# ScoutMakes_Azul.net
KiCad netlist of a schematic drawn in EAGLE
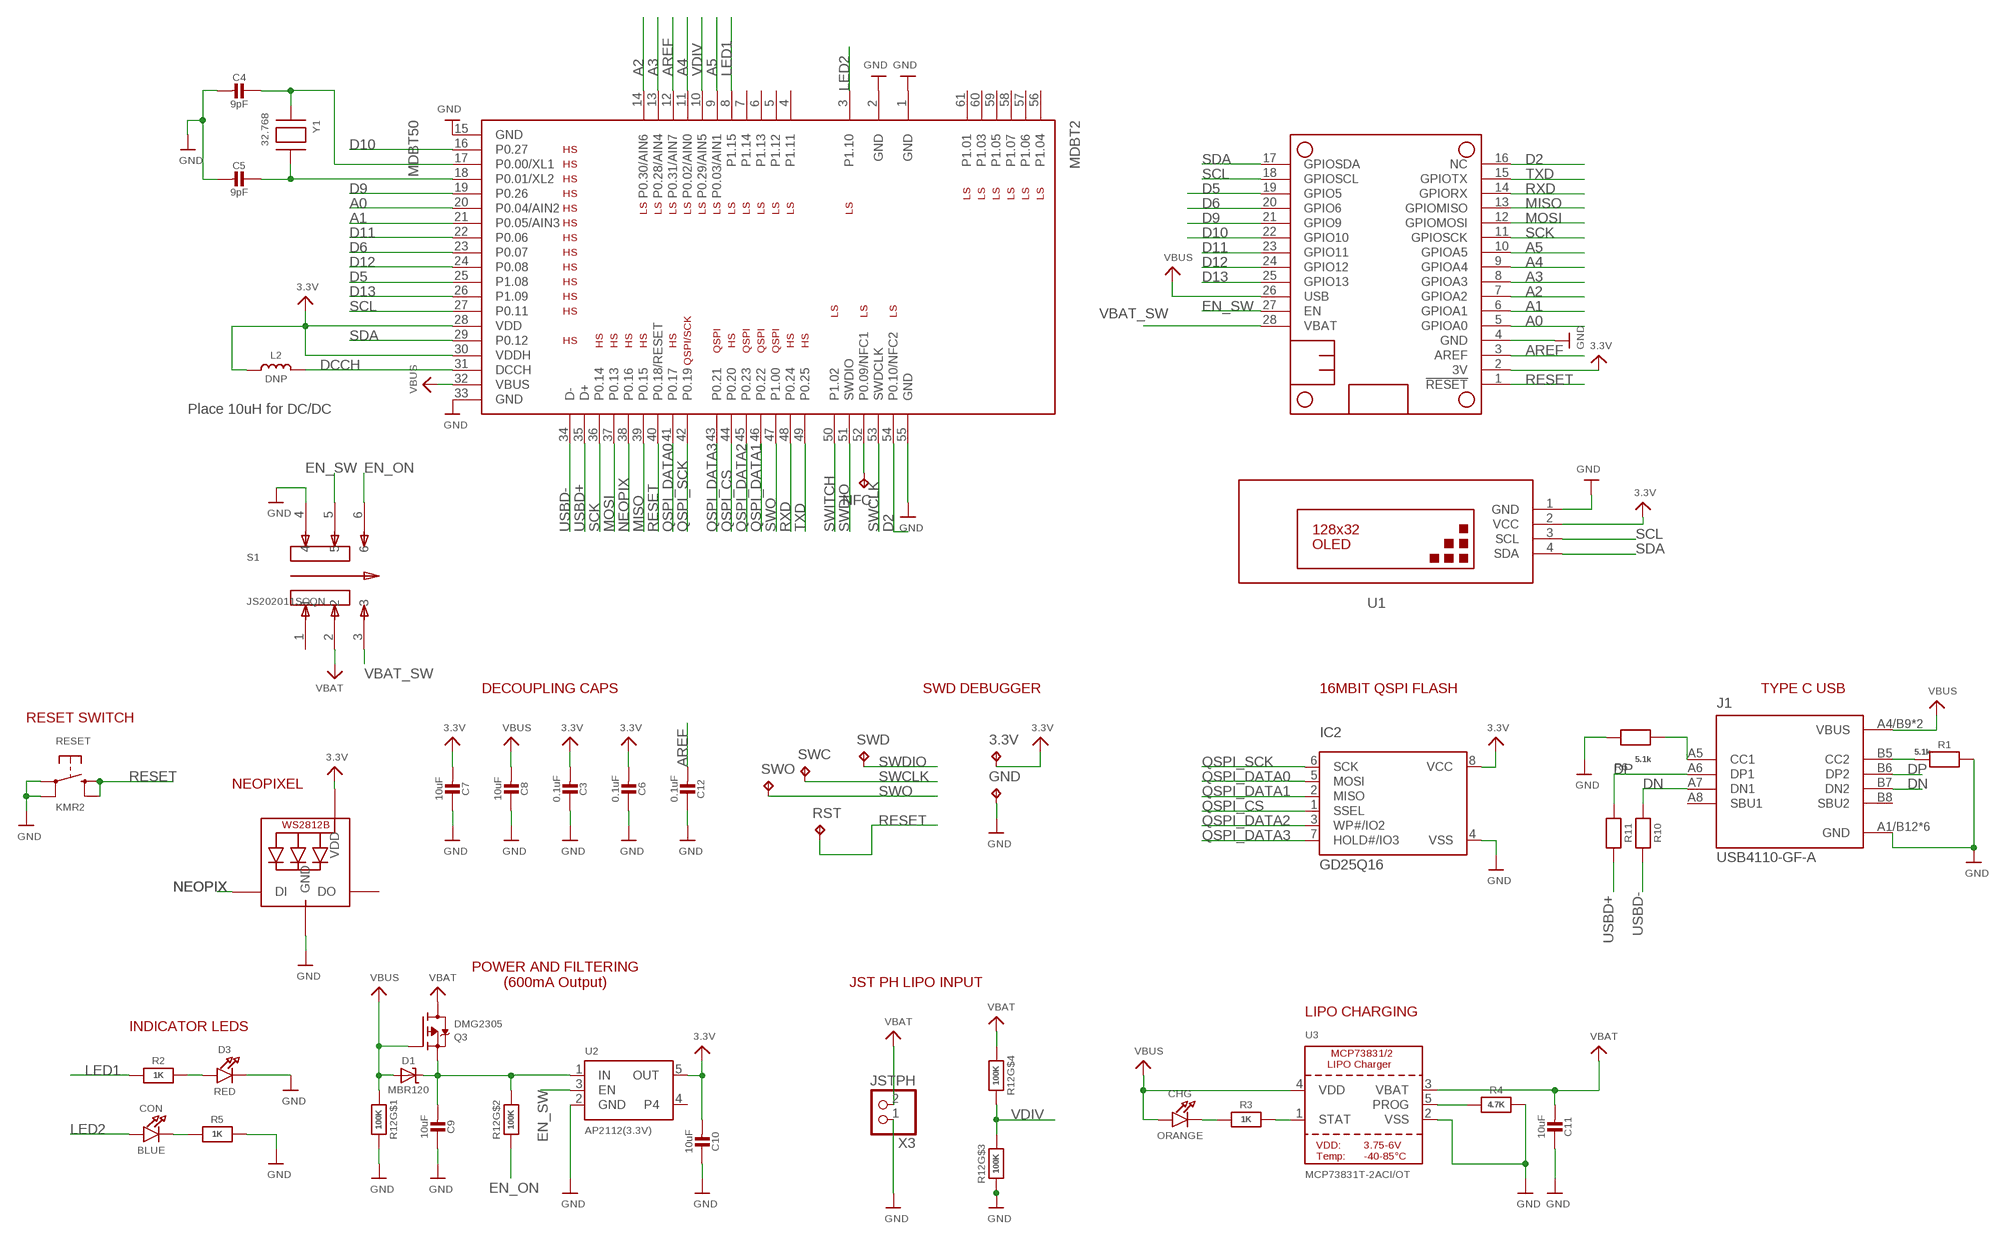
[diagram p0: schematic, sheet 1]

(export (version "E")
  (design (tool "Eeschema 10.0.6"))
  (components
    (comp (ref "3.3V")
      (value "TPTP12R")
      (footprint "eagle-import:TP12R")
      (libsource (lib "eagle-import") (part "TPTP12R"))
    )
    (comp (ref "C3")
      (value "0.1uF")
      (footprint "eagle-import:0603-NO")
      (libsource (lib "eagle-import") (part "CAP_CERAMIC0603_NO"))
    )
    (comp (ref "C4")
      (value "9pF")
      (footprint "eagle-import:0603-NO")
      (libsource (lib "eagle-import") (part "CAP_CERAMIC0603_NO"))
    )
    (comp (ref "C5")
      (value "9pF")
      (footprint "eagle-import:0603-NO")
      (libsource (lib "eagle-import") (part "CAP_CERAMIC0603_NO"))
    )
    (comp (ref "C6")
      (value "0.1uF")
      (footprint "eagle-import:0603-NO")
      (libsource (lib "eagle-import") (part "CAP_CERAMIC0603_NO"))
    )
    (comp (ref "C7")
      (value "10uF")
      (footprint "eagle-import:0805-NO")
      (libsource (lib "eagle-import") (part "CAP_CERAMIC0805-NOOUTLINE"))
    )
    (comp (ref "C8")
      (value "10uF")
      (footprint "eagle-import:0805-NO")
      (libsource (lib "eagle-import") (part "CAP_CERAMIC0805-NOOUTLINE"))
    )
    (comp (ref "C9")
      (value "10uF")
      (footprint "eagle-import:0805-NO")
      (libsource (lib "eagle-import") (part "CAP_CERAMIC0805-NOOUTLINE"))
    )
    (comp (ref "C10")
      (value "10uF")
      (footprint "eagle-import:0805-NO")
      (libsource (lib "eagle-import") (part "CAP_CERAMIC0805-NOOUTLINE"))
    )
    (comp (ref "C11")
      (value "10uF")
      (footprint "eagle-import:0805-NO")
      (libsource (lib "eagle-import") (part "CAP_CERAMIC0805-NOOUTLINE"))
    )
    (comp (ref "C12")
      (value "0.1uF")
      (footprint "eagle-import:0603-NO")
      (libsource (lib "eagle-import") (part "CAP_CERAMIC0603_NO"))
    )
    (comp (ref "CHG")
      (value "ORANGE")
      (footprint "eagle-import:CHIPLED_0805_NOOUTLINE")
      (libsource (lib "eagle-import") (part "LED0805_NOOUTLINE"))
    )
    (comp (ref "CON")
      (value "BLUE")
      (footprint "eagle-import:CHIPLED_0805_NOOUTLINE")
      (libsource (lib "eagle-import") (part "LED0805_NOOUTLINE"))
    )
    (comp (ref "D1")
      (value "MBR120")
      (footprint "eagle-import:SOD-123")
      (libsource (lib "eagle-import") (part "DIODE-SCHOTTKYSOD-123"))
    )
    (comp (ref "D3")
      (value "RED")
      (footprint "eagle-import:CHIPLED_0805_NOOUTLINE")
      (libsource (lib "eagle-import") (part "LED0805_NOOUTLINE"))
    )
    (comp (ref "GND")
      (value "TPTP12R")
      (footprint "eagle-import:TP12R")
      (libsource (lib "eagle-import") (part "TPTP12R"))
    )
    (comp (ref "IC2")
      (value "GD25Q16")
      (footprint "eagle-import:USON8")
      (libsource (lib "eagle-import") (part "SPIFLASH_8PINUX"))
    )
    (comp (ref "J1")
      (value "USB4110-GF-A")
      (footprint "eagle-import:GCT_USB4110-GF-A")
      (fields (field (name "MF") "GCT"))
      (libsource (lib "eagle-import") (part "USB4110-GF-A"))
    )
    (comp (ref "L2")
      (value "DNP")
      (footprint "eagle-import:_0805MP")
      (libsource (lib "eagle-import") (part "INDUCTOR_0805MP"))
    )
    (comp (ref "LED")
      (value "WS2812B3535")
      (footprint "eagle-import:LED3535")
      (libsource (lib "eagle-import") (part "WS2812B3535"))
    )
    (comp (ref "MDBT2")
      (value "MDBT50")
      (footprint "eagle-import:MDBT50")
      (libsource (lib "eagle-import") (part "MDBT50"))
    )
    (comp (ref "MS1")
      (value "FEATHERWING_NODIM")
      (footprint "eagle-import:FEATHERWING_NODIM")
      (libsource (lib "eagle-import") (part "FEATHERWING_NODIM"))
    )
    (comp (ref "NFC")
      (value "TPTP10R")
      (footprint "eagle-import:TP10R")
      (libsource (lib "eagle-import") (part "TPTP10R"))
    )
    (comp (ref "Q3")
      (value "DMG2305")
      (footprint "eagle-import:SOT23-R")
      (libsource (lib "eagle-import") (part "MOSFET-P"))
    )
    (comp (ref "R1")
      (value "5.1k")
      (footprint "eagle-import:0603-NO")
      (libsource (lib "eagle-import") (part "RESISTOR_0603_NOOUT"))
    )
    (comp (ref "R2")
      (value "1K")
      (footprint "eagle-import:0603-NO")
      (libsource (lib "eagle-import") (part "RESISTOR_0603_NOOUT"))
    )
    (comp (ref "R3")
      (value "1K")
      (footprint "eagle-import:0603-NO")
      (libsource (lib "eagle-import") (part "RESISTOR_0603_NOOUT"))
    )
    (comp (ref "R4")
      (value "4.7K")
      (footprint "eagle-import:0603-NO")
      (libsource (lib "eagle-import") (part "RESISTOR_0603_NOOUT"))
    )
    (comp (ref "R5")
      (value "1K")
      (footprint "eagle-import:0603-NO")
      (libsource (lib "eagle-import") (part "RESISTOR_0603_NOOUT"))
    )
    (comp (ref "R6")
      (value "5.1k")
      (footprint "eagle-import:0603-NO")
      (libsource (lib "eagle-import") (part "RESISTOR_0603_NOOUT"))
    )
    (comp (ref "R10")
      (value "22")
      (footprint "eagle-import:0603-NO")
      (libsource (lib "eagle-import") (part "RESISTOR_0603_NOOUT"))
    )
    (comp (ref "R11")
      (value "22")
      (footprint "eagle-import:0603-NO")
      (libsource (lib "eagle-import") (part "RESISTOR_0603_NOOUT"))
    )
    (comp (ref "R12")
      (value "100K")
      (footprint "eagle-import:RESPACK_4X0603")
      (libsource (lib "eagle-import") (part "RESISTOR_4PACK"))
    )
    (comp (ref "RESET")
      (value "KMR2")
      (footprint "eagle-import:BTN_KMR2_4.6X2.8")
      (libsource (lib "eagle-import") (part "SWITCH_TACT_SMT4.6X2.8"))
    )
    (comp (ref "RST")
      (value "TPTP12R")
      (footprint "eagle-import:TP12R")
      (libsource (lib "eagle-import") (part "TPTP12R"))
    )
    (comp (ref "S1")
      (value "JS202011SCQN")
      (footprint "eagle-import:SW_JS202011SCQN")
      (fields (field (name "DIGI-KEY_PART_NUMBER") "401-2002-1-ND") (field (name "MF") "C&K"))
      (libsource (lib "eagle-import") (part "JS202011SCQN"))
    )
    (comp (ref "SWC")
      (value "TPTP12R")
      (footprint "eagle-import:TP12R")
      (libsource (lib "eagle-import") (part "TPTP12R"))
    )
    (comp (ref "SWD")
      (value "TPTP12R")
      (footprint "eagle-import:TP12R")
      (libsource (lib "eagle-import") (part "TPTP12R"))
    )
    (comp (ref "SWO")
      (value "TPTP12R")
      (footprint "eagle-import:TP12R")
      (libsource (lib "eagle-import") (part "TPTP12R"))
    )
    (comp (ref "U1")
      (value "DISPLAY-OLED-128X32")
      (footprint "eagle-import:DISPLAY-OLED-128X32")
      (libsource (lib "eagle-import") (part "DISPLAY-OLED-128X32"))
    )
    (comp (ref "U2")
      (value "AP2112(3.3V)")
      (footprint "eagle-import:SOT23-5")
      (libsource (lib "eagle-import") (part "VREG_SOT23-5"))
    )
    (comp (ref "U3")
      (value "MCP73831T-2ACI/OT")
      (footprint "eagle-import:SOT23-5")
      (libsource (lib "eagle-import") (part "MCP73831/2"))
    )
    (comp (ref "X3")
      (value "JSTPH")
      (footprint "eagle-import:JSTPH2")
      (libsource (lib "eagle-import") (part "CON_JST_PH_2PIN"))
    )
    (comp (ref "Y1")
      (value "32.768")
      (footprint "eagle-import:XTAL3215")
      (libsource (lib "eagle-import") (part "XTAL-3.2X1.5"))
    )
  )
  (nets
    (net (code "1") (name "/A0") (class "Default")
      (node (ref "MDBT2") (pin "20") (pinfunction "P0.04/AIN2_20") (pintype "bidirectional"))
      (node (ref "MS1") (pin "5") (pinfunction "GPIOA0_5") (pintype "bidirectional"))
    )
    (net (code "2") (name "/A1") (class "Default")
      (node (ref "MDBT2") (pin "21") (pinfunction "P0.05/AIN3_21") (pintype "bidirectional"))
      (node (ref "MS1") (pin "6") (pinfunction "GPIOA1_6") (pintype "bidirectional"))
    )
    (net (code "3") (name "/A2") (class "Default")
      (node (ref "MDBT2") (pin "14") (pinfunction "P0.30/AIN6_14") (pintype "bidirectional"))
      (node (ref "MS1") (pin "7") (pinfunction "GPIOA2_7") (pintype "bidirectional"))
    )
    (net (code "4") (name "/A3") (class "Default")
      (node (ref "MDBT2") (pin "13") (pinfunction "P0.28/AIN4_13") (pintype "bidirectional"))
      (node (ref "MS1") (pin "8") (pinfunction "GPIOA3_8") (pintype "bidirectional"))
    )
    (net (code "5") (name "/A4") (class "Default")
      (node (ref "MDBT2") (pin "11") (pinfunction "P0.02/AIN0_11") (pintype "bidirectional"))
      (node (ref "MS1") (pin "9") (pinfunction "GPIOA4_9") (pintype "bidirectional"))
    )
    (net (code "6") (name "/A5") (class "Default")
      (node (ref "MDBT2") (pin "9") (pinfunction "P0.03/AIN1_9") (pintype "bidirectional"))
      (node (ref "MS1") (pin "10") (pinfunction "GPIOA5_10") (pintype "bidirectional"))
    )
    (net (code "7") (name "/AREF") (class "Default")
      (node (ref "C12") (pin "2") (pinfunction "2_2") (pintype "passive"))
      (node (ref "MDBT2") (pin "12") (pinfunction "P0.31/AIN7_12") (pintype "bidirectional"))
      (node (ref "MS1") (pin "3") (pinfunction "AREF_3") (pintype "passive"))
    )
    (net (code "8") (name "/D2") (class "Default")
      (node (ref "MDBT2") (pin "54") (pinfunction "P0.10/NFC2_54") (pintype "bidirectional"))
      (node (ref "MS1") (pin "16") (pinfunction "NC_16") (pintype "passive"))
    )
    (net (code "9") (name "/D5") (class "Default")
      (node (ref "MDBT2") (pin "25") (pinfunction "P1.08_25") (pintype "bidirectional"))
      (node (ref "MS1") (pin "19") (pinfunction "GPIO5_19") (pintype "bidirectional"))
    )
    (net (code "10") (name "/D6") (class "Default")
      (node (ref "MDBT2") (pin "23") (pinfunction "P0.07_23") (pintype "bidirectional"))
      (node (ref "MS1") (pin "20") (pinfunction "GPIO6_20") (pintype "bidirectional"))
    )
    (net (code "11") (name "/D9") (class "Default")
      (node (ref "MDBT2") (pin "19") (pinfunction "P0.26_19") (pintype "bidirectional"))
      (node (ref "MS1") (pin "21") (pinfunction "GPIO9_21") (pintype "bidirectional"))
    )
    (net (code "12") (name "/D10") (class "Default")
      (node (ref "MDBT2") (pin "16") (pinfunction "P0.27_16") (pintype "bidirectional"))
      (node (ref "MS1") (pin "22") (pinfunction "GPIO10_22") (pintype "bidirectional"))
    )
    (net (code "13") (name "/D11") (class "Default")
      (node (ref "MDBT2") (pin "22") (pinfunction "P0.06_22") (pintype "bidirectional"))
      (node (ref "MS1") (pin "23") (pinfunction "GPIO11_23") (pintype "bidirectional"))
    )
    (net (code "14") (name "/D12") (class "Default")
      (node (ref "MDBT2") (pin "24") (pinfunction "P0.08_24") (pintype "bidirectional"))
      (node (ref "MS1") (pin "24") (pinfunction "GPIO12_24") (pintype "bidirectional"))
    )
    (net (code "15") (name "/D13") (class "Default")
      (node (ref "MDBT2") (pin "26") (pinfunction "P1.09_26") (pintype "bidirectional"))
      (node (ref "MS1") (pin "25") (pinfunction "GPIO13_25") (pintype "bidirectional"))
    )
    (net (code "16") (name "/DCCH") (class "Default")
      (node (ref "L2") (pin "2") (pinfunction "2_2") (pintype "passive"))
      (node (ref "MDBT2") (pin "31") (pinfunction "DCCH_31") (pintype "bidirectional"))
    )
    (net (code "17") (name "/DN") (class "Default")
      (node (ref "J1") (pin "A7") (pinfunction "DN1_A7") (pintype "bidirectional"))
      (node (ref "J1") (pin "B7") (pinfunction "DN2_B7") (pintype "bidirectional"))
      (node (ref "R10") (pin "1") (pinfunction "1_1") (pintype "passive"))
    )
    (net (code "18") (name "/DP") (class "Default")
      (node (ref "J1") (pin "A6") (pinfunction "DP1_A6") (pintype "bidirectional"))
      (node (ref "J1") (pin "B6") (pinfunction "DP2_B6") (pintype "bidirectional"))
      (node (ref "R11") (pin "1") (pinfunction "1_1") (pintype "passive"))
    )
    (net (code "19") (name "/EN_ON") (class "Default")
      (node (ref "R12") (pin "2") (pinfunction "1_2") (pintype "passive"))
      (node (ref "S1") (pin "6") (pinfunction "6_6") (pintype "passive"))
    )
    (net (code "20") (name "/EN_SW") (class "Default")
      (node (ref "MS1") (pin "27") (pinfunction "EN_27") (pintype "passive"))
      (node (ref "S1") (pin "5") (pinfunction "5_5") (pintype "passive"))
      (node (ref "U2") (pin "3") (pinfunction "EN_3") (pintype "input"))
    )
    (net (code "21") (name "/LED1") (class "Default")
      (node (ref "MDBT2") (pin "8") (pinfunction "P1.15_8") (pintype "bidirectional"))
      (node (ref "R2") (pin "1") (pinfunction "1_1") (pintype "passive"))
    )
    (net (code "22") (name "/LED2") (class "Default")
      (node (ref "CON") (pin "A") (pinfunction "A_A") (pintype "passive"))
      (node (ref "MDBT2") (pin "3") (pinfunction "P1.10_3") (pintype "bidirectional"))
    )
    (net (code "23") (name "/MISO") (class "Default")
      (node (ref "MDBT2") (pin "39") (pinfunction "P0.15_39") (pintype "bidirectional"))
      (node (ref "MS1") (pin "13") (pinfunction "GPIOMISO_13") (pintype "bidirectional"))
    )
    (net (code "24") (name "/MOSI") (class "Default")
      (node (ref "MDBT2") (pin "37") (pinfunction "P0.13_37") (pintype "bidirectional"))
      (node (ref "MS1") (pin "12") (pinfunction "GPIOMOSI_12") (pintype "bidirectional"))
    )
    (net (code "25") (name "/NEOPIX") (class "Default")
      (node (ref "LED") (pin "1") (pinfunction "DI_1") (pintype "input"))
      (node (ref "MDBT2") (pin "38") (pinfunction "P0.16_38") (pintype "bidirectional"))
    )
    (net (code "26") (name "/QSPI_CS") (class "Default")
      (node (ref "IC2") (pin "1") (pinfunction "SSEL_1") (pintype "bidirectional"))
      (node (ref "MDBT2") (pin "44") (pinfunction "P0.20_44") (pintype "bidirectional"))
    )
    (net (code "27") (name "/QSPI_DATA0") (class "Default")
      (node (ref "IC2") (pin "5") (pinfunction "MOSI_5") (pintype "bidirectional"))
      (node (ref "MDBT2") (pin "41") (pinfunction "P0.17_41") (pintype "bidirectional"))
    )
    (net (code "28") (name "/QSPI_DATA1") (class "Default")
      (node (ref "IC2") (pin "2") (pinfunction "MISO_2") (pintype "bidirectional"))
      (node (ref "MDBT2") (pin "46") (pinfunction "P0.22_46") (pintype "bidirectional"))
    )
    (net (code "29") (name "/QSPI_DATA2") (class "Default")
      (node (ref "IC2") (pin "3") (pinfunction "WP#/IO2_3") (pintype "bidirectional"))
      (node (ref "MDBT2") (pin "45") (pinfunction "P0.23_45") (pintype "bidirectional"))
    )
    (net (code "30") (name "/QSPI_DATA3") (class "Default")
      (node (ref "IC2") (pin "7") (pinfunction "HOLD#/IO3_7") (pintype "bidirectional"))
      (node (ref "MDBT2") (pin "43") (pinfunction "P0.21_43") (pintype "bidirectional"))
    )
    (net (code "31") (name "/QSPI_SCK") (class "Default")
      (node (ref "IC2") (pin "6") (pinfunction "SCK_6") (pintype "bidirectional"))
      (node (ref "MDBT2") (pin "42") (pinfunction "P0.19_42") (pintype "bidirectional"))
    )
    (net (code "32") (name "/RESET") (class "Default")
      (node (ref "MDBT2") (pin "40") (pinfunction "P0.18/RESET_40") (pintype "bidirectional"))
      (node (ref "MS1") (pin "1") (pinfunction "~{RESET}_1") (pintype "input"))
      (node (ref "RESET") (pin "B") (pinfunction "S_B") (pintype "passive"))
      (node (ref "RESET") (pin "B'") (pinfunction "S1_B'") (pintype "passive"))
      (node (ref "RST") (pin "TP") (pinfunction "TP_TP") (pintype "input"))
    )
    (net (code "33") (name "/RXD") (class "Default")
      (node (ref "MDBT2") (pin "48") (pinfunction "P0.24_48") (pintype "bidirectional"))
      (node (ref "MS1") (pin "14") (pinfunction "GPIORX_14") (pintype "bidirectional"))
    )
    (net (code "34") (name "/SCK") (class "Default")
      (node (ref "MDBT2") (pin "36") (pinfunction "P0.14_36") (pintype "bidirectional"))
      (node (ref "MS1") (pin "11") (pinfunction "GPIOSCK_11") (pintype "bidirectional"))
    )
    (net (code "35") (name "/SCL") (class "Default")
      (node (ref "MDBT2") (pin "27") (pinfunction "P0.11_27") (pintype "bidirectional"))
      (node (ref "MS1") (pin "18") (pinfunction "GPIOSCL_18") (pintype "bidirectional"))
      (node (ref "U1") (pin "3") (pinfunction "SCL_3") (pintype "bidirectional"))
    )
    (net (code "36") (name "/SDA") (class "Default")
      (node (ref "MDBT2") (pin "29") (pinfunction "P0.12_29") (pintype "bidirectional"))
      (node (ref "MS1") (pin "17") (pinfunction "GPIOSDA_17") (pintype "bidirectional"))
      (node (ref "U1") (pin "4") (pinfunction "SDA_4") (pintype "bidirectional"))
    )
    (net (code "37") (name "/SWCLK") (class "Default")
      (node (ref "MDBT2") (pin "53") (pinfunction "SWDCLK_53") (pintype "bidirectional"))
      (node (ref "SWC") (pin "TP") (pinfunction "TP_TP") (pintype "input"))
    )
    (net (code "38") (name "/SWDIO") (class "Default")
      (node (ref "MDBT2") (pin "51") (pinfunction "SWDIO_51") (pintype "bidirectional"))
      (node (ref "SWD") (pin "TP") (pinfunction "TP_TP") (pintype "input"))
    )
    (net (code "39") (name "/SWITCH") (class "Default")
      (node (ref "MDBT2") (pin "50") (pinfunction "P1.02_50") (pintype "bidirectional"))
    )
    (net (code "40") (name "/SWO") (class "Default")
      (node (ref "MDBT2") (pin "47") (pinfunction "P1.00_47") (pintype "bidirectional"))
      (node (ref "SWO") (pin "TP") (pinfunction "TP_TP") (pintype "input"))
    )
    (net (code "41") (name "/TXD") (class "Default")
      (node (ref "MDBT2") (pin "49") (pinfunction "P0.25_49") (pintype "bidirectional"))
      (node (ref "MS1") (pin "15") (pinfunction "GPIOTX_15") (pintype "bidirectional"))
    )
    (net (code "42") (name "/USBD+") (class "Default")
      (node (ref "MDBT2") (pin "35") (pinfunction "D+_35") (pintype "bidirectional"))
      (node (ref "R11") (pin "2") (pinfunction "2_2") (pintype "passive"))
    )
    (net (code "43") (name "/USBD-") (class "Default")
      (node (ref "MDBT2") (pin "34") (pinfunction "D-_34") (pintype "bidirectional"))
      (node (ref "R10") (pin "2") (pinfunction "2_2") (pintype "passive"))
    )
    (net (code "44") (name "/VBAT_SW") (class "Default")
      (node (ref "MS1") (pin "28") (pinfunction "VBAT_28") (pintype "power_in"))
      (node (ref "S1") (pin "3") (pinfunction "3_3") (pintype "passive"))
    )
    (net (code "45") (name "/VDIV") (class "Default")
      (node (ref "MDBT2") (pin "10") (pinfunction "P0.29/AIN5_10") (pintype "bidirectional"))
      (node (ref "R12") (pin "5") (pinfunction "2_5") (pintype "passive"))
      (node (ref "R12") (pin "6") (pinfunction "2_6") (pintype "passive"))
    )
    (net (code "46") (name "3.3V") (class "Default")
      (node (ref "3.3V") (pin "TP") (pinfunction "TP_TP") (pintype "input"))
      (node (ref "C10") (pin "2") (pinfunction "2_2") (pintype "passive"))
      (node (ref "C3") (pin "2") (pinfunction "2_2") (pintype "passive"))
      (node (ref "C6") (pin "2") (pinfunction "2_2") (pintype "passive"))
      (node (ref "C7") (pin "2") (pinfunction "2_2") (pintype "passive"))
      (node (ref "IC2") (pin "8") (pinfunction "VCC_8") (pintype "bidirectional"))
      (node (ref "L2") (pin "1") (pinfunction "1_1") (pintype "passive"))
      (node (ref "LED") (pin "2") (pinfunction "VDD_2") (pintype "power_in"))
      (node (ref "MDBT2") (pin "28") (pinfunction "VDD_28") (pintype "bidirectional"))
      (node (ref "MDBT2") (pin "30") (pinfunction "VDDH_30") (pintype "bidirectional"))
      (node (ref "MS1") (pin "2") (pinfunction "3V_2") (pintype "power_in"))
      (node (ref "U1") (pin "2") (pinfunction "VCC_2") (pintype "power_in"))
      (node (ref "U2") (pin "5") (pinfunction "OUT_5") (pintype "power_in"))
    )
    (net (code "47") (name "GND") (class "Default")
      (node (ref "C10") (pin "1") (pinfunction "1_1") (pintype "passive"))
      (node (ref "C11") (pin "1") (pinfunction "1_1") (pintype "passive"))
      (node (ref "C12") (pin "1") (pinfunction "1_1") (pintype "passive"))
      (node (ref "C3") (pin "1") (pinfunction "1_1") (pintype "passive"))
      (node (ref "C4") (pin "2") (pinfunction "2_2") (pintype "passive"))
      (node (ref "C5") (pin "2") (pinfunction "2_2") (pintype "passive"))
      (node (ref "C6") (pin "1") (pinfunction "1_1") (pintype "passive"))
      (node (ref "C7") (pin "1") (pinfunction "1_1") (pintype "passive"))
      (node (ref "C8") (pin "1") (pinfunction "1_1") (pintype "passive"))
      (node (ref "C9") (pin "1") (pinfunction "1_1") (pintype "passive"))
      (node (ref "D3") (pin "C") (pinfunction "C_C") (pintype "passive"))
      (node (ref "GND") (pin "TP") (pinfunction "TP_TP") (pintype "input"))
      (node (ref "IC2") (pin "4") (pinfunction "VSS_4") (pintype "bidirectional"))
      (node (ref "J1") (pin "A1/B12") (pinfunction "GND_A1/B12") (pintype "power_in"))
      (node (ref "J1") (pin "B1/A12") (pinfunction "GND_B1/A12") (pintype "power_in"))
      (node (ref "J1") (pin "S1") (pinfunction "GND_S1") (pintype "power_in"))
      (node (ref "J1") (pin "S2") (pinfunction "GND_S2") (pintype "power_in"))
      (node (ref "J1") (pin "S3") (pinfunction "GND_S3") (pintype "power_in"))
      (node (ref "J1") (pin "S4") (pinfunction "GND_S4") (pintype "power_in"))
      (node (ref "LED") (pin "4") (pinfunction "GND_4") (pintype "power_in"))
      (node (ref "MDBT2") (pin "1") (pinfunction "GND_1") (pintype "bidirectional"))
      (node (ref "MDBT2") (pin "15") (pinfunction "GND_15") (pintype "bidirectional"))
      (node (ref "MDBT2") (pin "2") (pinfunction "GND_2") (pintype "bidirectional"))
      (node (ref "MDBT2") (pin "33") (pinfunction "GND_33") (pintype "bidirectional"))
      (node (ref "MDBT2") (pin "55") (pinfunction "GND_55") (pintype "bidirectional"))
      (node (ref "MS1") (pin "4") (pinfunction "GND_4") (pintype "power_in"))
      (node (ref "R1") (pin "2") (pinfunction "2_2") (pintype "passive"))
      (node (ref "R12") (pin "3") (pinfunction "1_3") (pintype "passive"))
      (node (ref "R12") (pin "8") (pinfunction "2_8") (pintype "passive"))
      (node (ref "R4") (pin "2") (pinfunction "2_2") (pintype "passive"))
      (node (ref "R5") (pin "2") (pinfunction "2_2") (pintype "passive"))
      (node (ref "R6") (pin "2") (pinfunction "2_2") (pintype "passive"))
      (node (ref "RESET") (pin "A") (pinfunction "P_A") (pintype "passive"))
      (node (ref "RESET") (pin "A'") (pinfunction "P1_A'") (pintype "passive"))
      (node (ref "S1") (pin "4") (pinfunction "4_4") (pintype "passive"))
      (node (ref "U1") (pin "1") (pinfunction "GND_1") (pintype "power_in"))
      (node (ref "U2") (pin "2") (pinfunction "GND_2") (pintype "power_in"))
      (node (ref "U3") (pin "2") (pinfunction "VSS_2") (pintype "power_in"))
      (node (ref "X3") (pin "1") (pinfunction "1_1") (pintype "passive"))
    )
    (net (code "48") (name "Net-(CHG-PadC)") (class "Default")
      (node (ref "CHG") (pin "C") (pinfunction "C_C") (pintype "passive"))
      (node (ref "R3") (pin "1") (pinfunction "1_1") (pintype "passive"))
    )
    (net (code "49") (name "Net-(CON-PadC)") (class "Default")
      (node (ref "CON") (pin "C") (pinfunction "C_C") (pintype "passive"))
      (node (ref "R5") (pin "1") (pinfunction "1_1") (pintype "passive"))
    )
    (net (code "50") (name "Net-(D3-PadA)") (class "Default")
      (node (ref "D3") (pin "A") (pinfunction "A_A") (pintype "passive"))
      (node (ref "R2") (pin "2") (pinfunction "2_2") (pintype "passive"))
    )
    (net (code "51") (name "Net-(J1-CC1)") (class "Default")
      (node (ref "J1") (pin "A5") (pinfunction "CC1_A5") (pintype "bidirectional"))
      (node (ref "R6") (pin "1") (pinfunction "1_1") (pintype "passive"))
    )
    (net (code "52") (name "Net-(J1-CC2)") (class "Default")
      (node (ref "J1") (pin "B5") (pinfunction "CC2_B5") (pintype "bidirectional"))
      (node (ref "R1") (pin "1") (pinfunction "1_1") (pintype "passive"))
    )
    (net (code "53") (name "Net-(MDBT2-P0.00{slash}XL1)") (class "Default")
      (node (ref "C4") (pin "1") (pinfunction "1_1") (pintype "passive"))
      (node (ref "MDBT2") (pin "17") (pinfunction "P0.00/XL1_17") (pintype "bidirectional"))
      (node (ref "Y1") (pin "P$1") (pinfunction "P$1_P$1") (pintype "bidirectional"))
    )
    (net (code "54") (name "Net-(MDBT2-P0.01{slash}XL2)") (class "Default")
      (node (ref "C5") (pin "1") (pinfunction "1_1") (pintype "passive"))
      (node (ref "MDBT2") (pin "18") (pinfunction "P0.01/XL2_18") (pintype "bidirectional"))
      (node (ref "Y1") (pin "P$2") (pinfunction "P$2_P$2") (pintype "bidirectional"))
    )
    (net (code "55") (name "Net-(MDBT2-P0.09{slash}NFC1)") (class "Default")
      (node (ref "MDBT2") (pin "52") (pinfunction "P0.09/NFC1_52") (pintype "bidirectional"))
      (node (ref "NFC") (pin "TP") (pinfunction "TP_TP") (pintype "input"))
    )
    (net (code "56") (name "Net-(Q3-S)") (class "Default")
      (node (ref "C9") (pin "2") (pinfunction "2_2") (pintype "passive"))
      (node (ref "D1") (pin "C") (pinfunction "C_C") (pintype "passive"))
      (node (ref "Q3") (pin "2") (pinfunction "S_2") (pintype "passive"))
      (node (ref "R12") (pin "7") (pinfunction "2_7") (pintype "passive"))
      (node (ref "U2") (pin "1") (pinfunction "IN_1") (pintype "power_in"))
    )
    (net (code "57") (name "Net-(U3-PROG)") (class "Default")
      (node (ref "R4") (pin "1") (pinfunction "1_1") (pintype "passive"))
      (node (ref "U3") (pin "5") (pinfunction "PROG_5") (pintype "input"))
    )
    (net (code "58") (name "Net-(U3-STAT)") (class "Default")
      (node (ref "R3") (pin "2") (pinfunction "2_2") (pintype "passive"))
      (node (ref "U3") (pin "1") (pinfunction "STAT_1") (pintype "output"))
    )
    (net (code "59") (name "VBAT") (class "Default")
      (node (ref "C11") (pin "2") (pinfunction "2_2") (pintype "passive"))
      (node (ref "Q3") (pin "3") (pinfunction "D_3") (pintype "passive"))
      (node (ref "R12") (pin "4") (pinfunction "1_4") (pintype "passive"))
      (node (ref "S1") (pin "2") (pinfunction "2_2") (pintype "passive"))
      (node (ref "U3") (pin "3") (pinfunction "VBAT_3") (pintype "power_in"))
      (node (ref "X3") (pin "2") (pinfunction "2_2") (pintype "passive"))
    )
    (net (code "60") (name "VBUS") (class "Default")
      (node (ref "C8") (pin "2") (pinfunction "2_2") (pintype "passive"))
      (node (ref "CHG") (pin "A") (pinfunction "A_A") (pintype "passive"))
      (node (ref "D1") (pin "A") (pinfunction "A_A") (pintype "passive"))
      (node (ref "J1") (pin "A4/B9") (pinfunction "VBUS_A4/B9") (pintype "power_in"))
      (node (ref "J1") (pin "B4/A9") (pinfunction "VBUS_B4/A9") (pintype "power_in"))
      (node (ref "MDBT2") (pin "32") (pinfunction "VBUS_32") (pintype "bidirectional"))
      (node (ref "MS1") (pin "26") (pinfunction "USB_26") (pintype "power_in"))
      (node (ref "Q3") (pin "1") (pinfunction "G_1") (pintype "passive"))
      (node (ref "R12") (pin "1") (pinfunction "1_1") (pintype "passive"))
      (node (ref "U3") (pin "4") (pinfunction "VDD_4") (pintype "power_in"))
    )
    (net (code "61") (name "unconnected-(J1-SBU1-PadA8)") (class "Default")
      (node (ref "J1") (pin "A8") (pinfunction "SBU1_A8") (pintype "bidirectional"))
    )
    (net (code "62") (name "unconnected-(J1-SBU2-PadB8)") (class "Default")
      (node (ref "J1") (pin "B8") (pinfunction "SBU2_B8") (pintype "bidirectional"))
    )
    (net (code "63") (name "unconnected-(LED-DO-Pad3)") (class "Default")
      (node (ref "LED") (pin "3") (pinfunction "DO_3") (pintype "output"))
    )
    (net (code "64") (name "unconnected-(MDBT2-P1.01-Pad61)") (class "Default")
      (node (ref "MDBT2") (pin "61") (pinfunction "P1.01_61") (pintype "bidirectional"))
    )
    (net (code "65") (name "unconnected-(MDBT2-P1.03-Pad60)") (class "Default")
      (node (ref "MDBT2") (pin "60") (pinfunction "P1.03_60") (pintype "bidirectional"))
    )
    (net (code "66") (name "unconnected-(MDBT2-P1.04-Pad56)") (class "Default")
      (node (ref "MDBT2") (pin "56") (pinfunction "P1.04_56") (pintype "bidirectional"))
    )
    (net (code "67") (name "unconnected-(MDBT2-P1.05-Pad59)") (class "Default")
      (node (ref "MDBT2") (pin "59") (pinfunction "P1.05_59") (pintype "bidirectional"))
    )
    (net (code "68") (name "unconnected-(MDBT2-P1.06-Pad57)") (class "Default")
      (node (ref "MDBT2") (pin "57") (pinfunction "P1.06_57") (pintype "bidirectional"))
    )
    (net (code "69") (name "unconnected-(MDBT2-P1.07-Pad58)") (class "Default")
      (node (ref "MDBT2") (pin "58") (pinfunction "P1.07_58") (pintype "bidirectional"))
    )
    (net (code "70") (name "unconnected-(MDBT2-P1.11-Pad4)") (class "Default")
      (node (ref "MDBT2") (pin "4") (pinfunction "P1.11_4") (pintype "bidirectional"))
    )
    (net (code "71") (name "unconnected-(MDBT2-P1.12-Pad5)") (class "Default")
      (node (ref "MDBT2") (pin "5") (pinfunction "P1.12_5") (pintype "bidirectional"))
    )
    (net (code "72") (name "unconnected-(MDBT2-P1.13-Pad6)") (class "Default")
      (node (ref "MDBT2") (pin "6") (pinfunction "P1.13_6") (pintype "bidirectional"))
    )
    (net (code "73") (name "unconnected-(MDBT2-P1.14-Pad7)") (class "Default")
      (node (ref "MDBT2") (pin "7") (pinfunction "P1.14_7") (pintype "bidirectional"))
    )
    (net (code "74") (name "unconnected-(S1-Pad1)") (class "Default")
      (node (ref "S1") (pin "1") (pinfunction "1_1") (pintype "passive"))
    )
    (net (code "75") (name "unconnected-(U2-P4-Pad4)") (class "Default")
      (node (ref "U2") (pin "4") (pinfunction "P4_4") (pintype "bidirectional"))
    )
  )
)
